# STM32G473CET6_PINOUT.net
KiCad netlist of a schematic drawn in Altium Designer
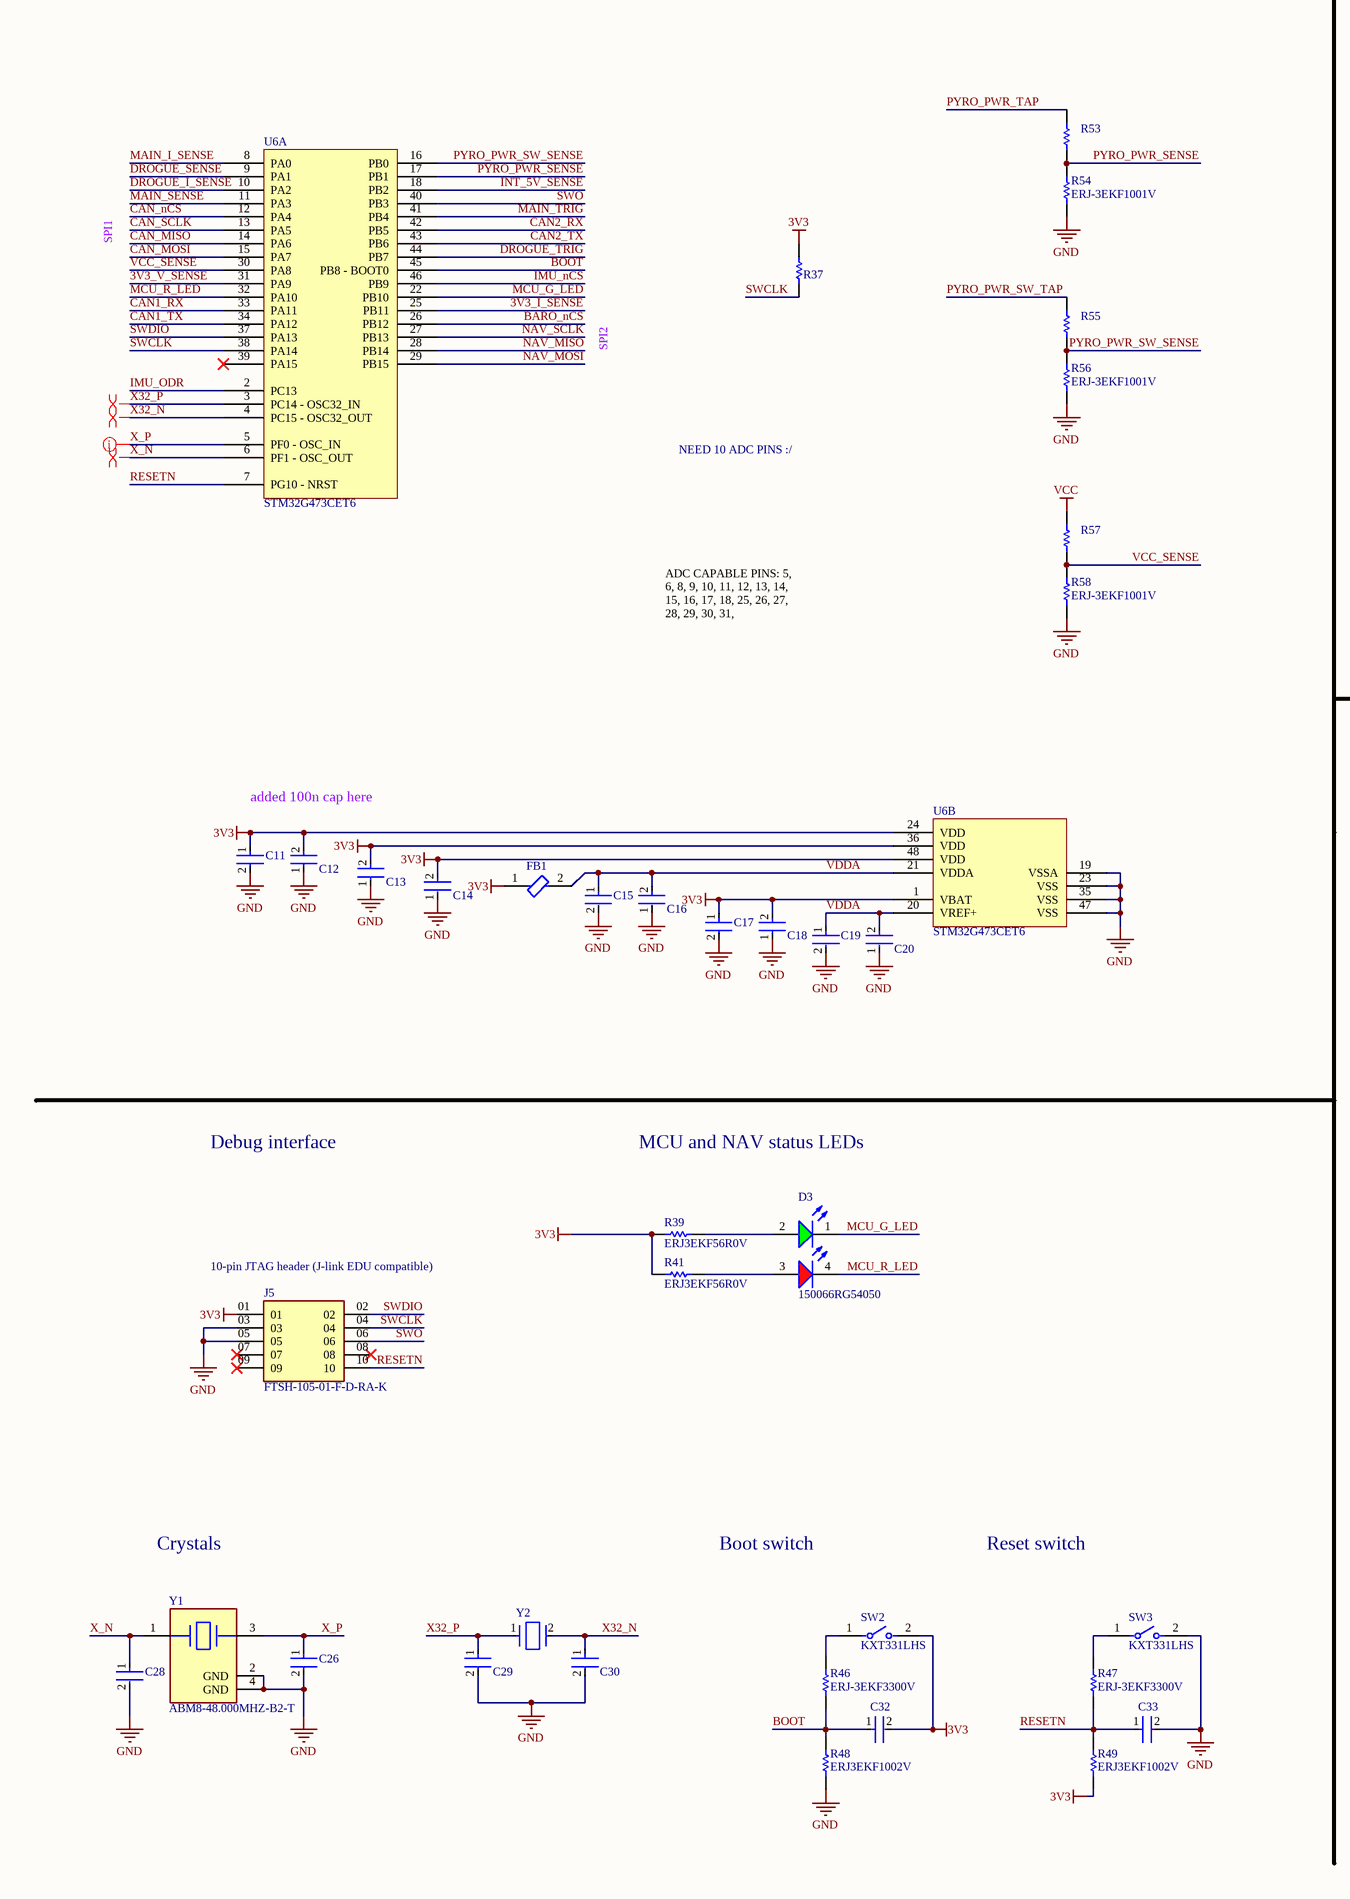
[diagram p0: STM32G473CET6_PINOUT.SchDoc, left]
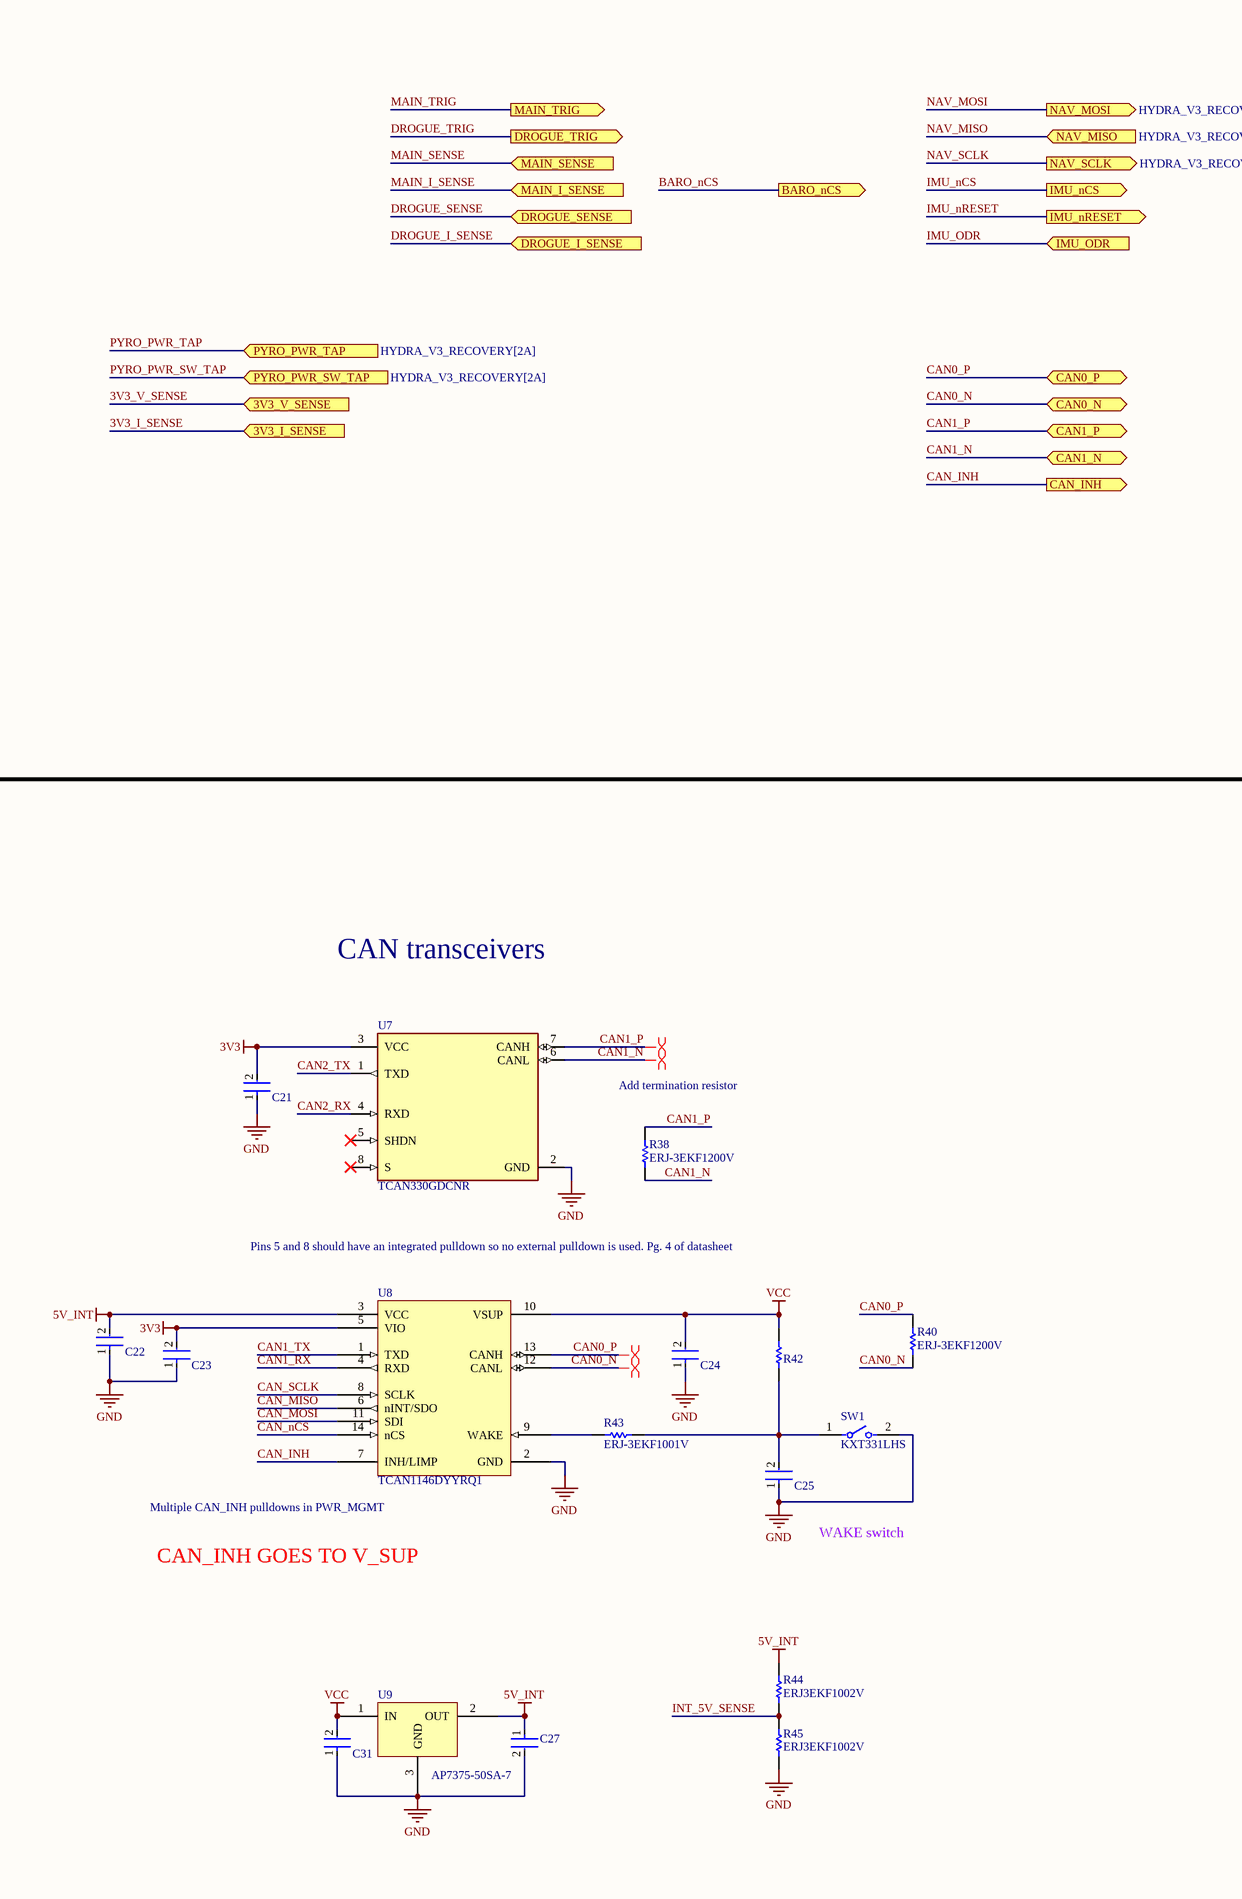
[diagram p1: STM32G473CET6_PINOUT.SchDoc, right]

(export (version "E")
  (design (tool "Eeschema 10.0.6"))
  (components
    (comp (ref "C11")
      (value "C1005X5R1A475K050BC")
      (footprint "FP-C1005-050-0_15-MFG")
      (description "CAP CER 4.7UF 10V X5R 0402")
      (fields (field (name "TOLERANCE") "10%"))
      (libsource (lib "Altium Content Vault") (part "b4654b650e69147ec39a6b967a45e02"))
    )
    (comp (ref "C12")
      (value "GRM155R71C104KA88D")
      (footprint "FP-GRM15-MFG")
      (description "CAP CER 0.1UF 16V X7R 0402")
      (fields
        (field (name "TOLERANCE") "10%")
        (field (name "OCTOPART") "https://octopart.com/grm155r71c104ka88d-murata-196880")
      )
      (libsource (lib "Altium Content Vault") (part "236180d848d6139a670b325ea6854c9"))
    )
    (comp (ref "C13")
      (value "GRM155R71C104KA88D")
      (footprint "FP-GRM15-MFG")
      (description "CAP CER 0.1UF 16V X7R 0402")
      (fields
        (field (name "TOLERANCE") "10%")
        (field (name "OCTOPART") "https://octopart.com/grm155r71c104ka88d-murata-196880")
      )
      (libsource (lib "Altium Content Vault") (part "236180d848d6139a670b325ea6854c9"))
    )
    (comp (ref "C14")
      (value "GRM155R71C104KA88D")
      (footprint "FP-GRM15-MFG")
      (description "CAP CER 0.1UF 16V X7R 0402")
      (fields
        (field (name "TOLERANCE") "10%")
        (field (name "OCTOPART") "https://octopart.com/grm155r71c104ka88d-murata-196880")
      )
      (libsource (lib "Altium Content Vault") (part "236180d848d6139a670b325ea6854c9"))
    )
    (comp (ref "C15")
      (value "EMK105BJ105KV-F")
      (footprint "FP-0402-L_1_0_0_05-W_0_5-IPC_A")
      (description "None")
      (fields (field (name "TOLERANCE") "10%"))
      (libsource (lib "Altium Content Vault") (part "b4654b650e69147ec39a6b967a45e02"))
    )
    (comp (ref "C16")
      (value "GRM155R71C104KA88D")
      (footprint "FP-GRM15-MFG")
      (description "CAP CER 0.1UF 16V X7R 0402")
      (fields
        (field (name "TOLERANCE") "10%")
        (field (name "OCTOPART") "https://octopart.com/grm155r71c104ka88d-murata-196880")
      )
      (libsource (lib "Altium Content Vault") (part "236180d848d6139a670b325ea6854c9"))
    )
    (comp (ref "C17")
      (value "EMK105BJ105KV-F")
      (footprint "FP-0402-L_1_0_0_05-W_0_5-IPC_A")
      (description "None")
      (fields (field (name "TOLERANCE") "10%"))
      (libsource (lib "Altium Content Vault") (part "b4654b650e69147ec39a6b967a45e02"))
    )
    (comp (ref "C18")
      (value "GRM155R71C104KA88D")
      (footprint "FP-GRM15-MFG")
      (description "CAP CER 0.1UF 16V X7R 0402")
      (fields
        (field (name "TOLERANCE") "10%")
        (field (name "OCTOPART") "https://octopart.com/grm155r71c104ka88d-murata-196880")
      )
      (libsource (lib "Altium Content Vault") (part "236180d848d6139a670b325ea6854c9"))
    )
    (comp (ref "C19")
      (value "EMK105BJ105KV-F")
      (footprint "FP-0402-L_1_0_0_05-W_0_5-IPC_A")
      (description "None")
      (fields (field (name "TOLERANCE") "10%"))
      (libsource (lib "Altium Content Vault") (part "b4654b650e69147ec39a6b967a45e02"))
    )
    (comp (ref "C20")
      (value "GRM155R71C104KA88D")
      (footprint "FP-GRM15-MFG")
      (description "CAP CER 0.1UF 16V X7R 0402")
      (fields
        (field (name "TOLERANCE") "10%")
        (field (name "OCTOPART") "https://octopart.com/grm155r71c104ka88d-murata-196880")
      )
      (libsource (lib "Altium Content Vault") (part "236180d848d6139a670b325ea6854c9"))
    )
    (comp (ref "C21")
      (value "C0402C104K8PACTU")
      (footprint "FP-C0402-BB-MFG")
      (description "CAP CER 0.1UF 10V X5R 0402")
      (fields (field (name "MANUFACTURER") "Kemet") (field (name "TOLERANCE") "0.1"))
      (libsource (lib "Altium Content Vault") (part "b4654b650e69147ec39a6b967a45e02"))
    )
    (comp (ref "C22")
      (value "C0402C104K8PACTU")
      (footprint "FP-C0402-BB-MFG")
      (description "CAP CER 0.1UF 10V X5R 0402")
      (fields (field (name "MANUFACTURER") "Kemet") (field (name "TOLERANCE") "0.1"))
      (libsource (lib "Altium Content Vault") (part "b4654b650e69147ec39a6b967a45e02"))
    )
    (comp (ref "C23")
      (value "C0402C104K8PACTU")
      (footprint "FP-C0402-BB-MFG")
      (description "CAP CER 0.1UF 10V X5R 0402")
      (fields (field (name "MANUFACTURER") "Kemet") (field (name "TOLERANCE") "0.1"))
      (libsource (lib "Altium Content Vault") (part "b4654b650e69147ec39a6b967a45e02"))
    )
    (comp (ref "C24")
      (value "C0402C104K8PACTU")
      (footprint "FP-C0402-BB-MFG")
      (description "CAP CER 0.1UF 10V X5R 0402")
      (fields (field (name "MANUFACTURER") "Kemet") (field (name "TOLERANCE") "0.1"))
      (libsource (lib "Altium Content Vault") (part "b4654b650e69147ec39a6b967a45e02"))
    )
    (comp (ref "C25")
      (value "C0402C104K8PACTU")
      (footprint "FP-C0402-BB-MFG")
      (description "CAP CER 0.1UF 10V X5R 0402")
      (fields (field (name "MANUFACTURER") "Kemet") (field (name "TOLERANCE") "0.1"))
      (libsource (lib "Altium Content Vault") (part "b4654b650e69147ec39a6b967a45e02"))
    )
    (comp (ref "C26")
      (value "C0402C689C5GACTU")
      (footprint "FP-C0402-BB-MFG")
      (description "CAP CER 6.8PF 50V NP0 0402")
      (fields
        (field (name "OCTOPART") "https://octopart.com/c0402c689c5gactu-kemet-9143567")
        (field (name "MANUFACTURER") "Kemet")
      )
      (libsource (lib "Altium Content Vault") (part "b4654b650e69147ec39a6b967a45e02"))
    )
    (comp (ref "C27")
      (value "CL05A106MP5NUNC")
      (footprint "FP-CL05A106MP5NUNC-MFG")
      (description "CAP CER 10UF 10V X5R 0402")
      (fields
        (field (name "OCTOPART") "https://octopart.com/cl05a106mp5nunc-samsung-22457395")
        (field (name "TOLERANCE") "20%")
      )
      (libsource (lib "Altium Content Vault") (part "b4654b650e69147ec39a6b967a45e02"))
    )
    (comp (ref "C28")
      (value "C0402C689C5GACTU")
      (footprint "FP-C0402-BB-MFG")
      (description "CAP CER 6.8PF 50V NP0 0402")
      (fields
        (field (name "OCTOPART") "https://octopart.com/c0402c689c5gactu-kemet-9143567")
        (field (name "MANUFACTURER") "Kemet")
      )
      (libsource (lib "Altium Content Vault") (part "b4654b650e69147ec39a6b967a45e02"))
    )
    (comp (ref "C29")
      (value "04025A180FAT2A")
      (footprint "FP-0402-L_1_0_1-W_0_5_0_1-IPC_A")
      (description "General Purpose Ceramic Capacitor, 0402, 18pF, 1%, C0G, 30ppm/°C, 50V")
      (fields (field (name "TOLERANCE") "1%"))
      (libsource (lib "Altium Content Vault") (part "b4654b650e69147ec39a6b967a45e02"))
    )
    (comp (ref "C30")
      (value "04025A180FAT2A")
      (footprint "FP-0402-L_1_0_1-W_0_5_0_1-IPC_A")
      (description "General Purpose Ceramic Capacitor, 0402, 18pF, 1%, C0G, 30ppm/°C, 50V")
      (fields (field (name "TOLERANCE") "1%"))
      (libsource (lib "Altium Content Vault") (part "b4654b650e69147ec39a6b967a45e02"))
    )
    (comp (ref "C31")
      (value "C0402C104K8PACTU")
      (footprint "FP-C0402-BB-MFG")
      (description "CAP CER 0.1UF 10V X5R 0402")
      (fields (field (name "MANUFACTURER") "Kemet") (field (name "TOLERANCE") "0.1"))
      (libsource (lib "Altium Content Vault") (part "b4654b650e69147ec39a6b967a45e02"))
    )
    (comp (ref "C32")
      (value "C0402C104K8PACTU")
      (footprint "FP-C0402-BB-MFG")
      (description "CAP CER 0.1UF 10V X5R 0402")
      (fields (field (name "MANUFACTURER") "Kemet") (field (name "TOLERANCE") "0.1"))
      (libsource (lib "Altium Content Vault") (part "b4654b650e69147ec39a6b967a45e02"))
    )
    (comp (ref "C33")
      (value "C0402C104K8PACTU")
      (footprint "FP-C0402-BB-MFG")
      (description "CAP CER 0.1UF 10V X5R 0402")
      (fields (field (name "MANUFACTURER") "Kemet") (field (name "TOLERANCE") "0.1"))
      (libsource (lib "Altium Content Vault") (part "b4654b650e69147ec39a6b967a45e02"))
    )
    (comp (ref "D3")
      (value "150066RG54050")
      (footprint "WL-SBCD_0606")
      (description "Led, Red/Grn, 180Mcd/230Mcd, 624Nm/525Nm Rohs Compliant: Yes")
      (fields (field (name "SOURCE") "rgled.SchLib"))
      (libsource (lib "Space Concordia") (part "CMP-004-00034-2"))
    )
    (comp (ref "FB1")
      (value "BLM15PX601SN1D")
      (footprint "FP-BLM15-0_05-MFG")
      (description "Chip Ferrite Bead, 0402, 600Ω @ 100MHz, 0.23Ω, 25%, 900mA")
      (fields (field (name "TOLERANCE") "25%"))
      (libsource (lib "Altium Content Vault") (part "5f30dd21d616792df468990f7003faa"))
    )
    (comp (ref "J5")
      (value "FTSH-105-01-F-D-RA-K")
      (footprint "FTSH-105-01-F-D-RA-K-Footprint-1")
      (libsource (lib "Space Concordia") (part "FTSH-105-01-F-D-RA-K-Symbol-1"))
    )
    (comp (ref "R37")
      (value "ERJ3EKF1002V")
      (footprint "RESC1609X55X30LL15T15")
      (description "Chip Resistor, 10 KOhm, +/- 1%, 0.1 W, -55 to 155 degC, 0603 (1608 Metric), RoHS, Tape and Reel")
      (fields (field (name "TOLERANCE") "1%") (field (name "MANUFACTURER") "Panasonic"))
      (libsource (lib "Altium Content Vault") (part "RES-2"))
    )
    (comp (ref "R38")
      (value "ERJ-3EKF1200V")
      (footprint "RESC1609X55X30ML15T15")
      (description "Chip Resistor, 120 Ohm, +/- 1%, 0.1 W, -55 to 155 degC, 0603 (1608 Metric), RoHS, Tape and Reel")
      (fields (field (name "TOLERANCE") "1%") (field (name "MANUFACTURER") "Panasonic"))
      (libsource (lib "Altium Content Vault") (part "RES-2"))
    )
    (comp (ref "R39")
      (value "ERJ3EKF56R0V")
      (footprint "RESC1608X55X30NL15T15")
      (fields (field (name "MANUFACTURER") "Panasonic"))
      (libsource (lib "Altium Content Vault") (part "RES"))
    )
    (comp (ref "R40")
      (value "ERJ-3EKF1200V")
      (footprint "RESC1609X55X30ML15T15")
      (description "Chip Resistor, 120 Ohm, +/- 1%, 0.1 W, -55 to 155 degC, 0603 (1608 Metric), RoHS, Tape and Reel")
      (fields (field (name "TOLERANCE") "1%") (field (name "MANUFACTURER") "Panasonic"))
      (libsource (lib "Altium Content Vault") (part "RES-2"))
    )
    (comp (ref "R41")
      (value "ERJ3EKF56R0V")
      (footprint "RESC1608X55X30NL15T15")
      (fields (field (name "MANUFACTURER") "Panasonic"))
      (libsource (lib "Altium Content Vault") (part "RES"))
    )
    (comp (ref "R42")
      (value "ERJ3EKF1002V")
      (footprint "RESC1609X55X30LL15T15")
      (description "Chip Resistor, 10 KOhm, +/- 1%, 0.1 W, -55 to 155 degC, 0603 (1608 Metric), RoHS, Tape and Reel")
      (fields (field (name "TOLERANCE") "1%") (field (name "MANUFACTURER") "Panasonic"))
      (libsource (lib "Altium Content Vault") (part "RES-2"))
    )
    (comp (ref "R43")
      (value "ERJ-3EKF1001V")
      (footprint "RESC1608X55X30LL15T15")
      (fields (field (name "MANUFACTURER") "Panasonic"))
      (libsource (lib "Altium Content Vault") (part "RES"))
    )
    (comp (ref "R44")
      (value "ERJ3EKF1002V")
      (footprint "RESC1609X55X30LL15T15")
      (description "Chip Resistor, 10 KOhm, +/- 1%, 0.1 W, -55 to 155 degC, 0603 (1608 Metric), RoHS, Tape and Reel")
      (fields (field (name "TOLERANCE") "1%") (field (name "MANUFACTURER") "Panasonic"))
      (libsource (lib "Altium Content Vault") (part "RES-2"))
    )
    (comp (ref "R45")
      (value "ERJ3EKF1002V")
      (footprint "RESC1609X55X30LL15T15")
      (description "Chip Resistor, 10 KOhm, +/- 1%, 0.1 W, -55 to 155 degC, 0603 (1608 Metric), RoHS, Tape and Reel")
      (fields (field (name "TOLERANCE") "1%") (field (name "MANUFACTURER") "Panasonic"))
      (libsource (lib "Altium Content Vault") (part "RES-2"))
    )
    (comp (ref "R46")
      (value "ERJ-3EKF3300V")
      (footprint "RESC1608X55X30LL15T15")
      (description "Chip Resistor, 330 Ohm, +/- 1%, 0.1 W, -55 to 155 degC, 0603 (1608 Metric), RoHS, Tape and Reel")
      (libsource (lib "Altium Content Vault") (part "RES-2"))
    )
    (comp (ref "R47")
      (value "ERJ-3EKF3300V")
      (footprint "RESC1608X55X30LL15T15")
      (description "Chip Resistor, 330 Ohm, +/- 1%, 0.1 W, -55 to 155 degC, 0603 (1608 Metric), RoHS, Tape and Reel")
      (libsource (lib "Altium Content Vault") (part "RES-2"))
    )
    (comp (ref "R48")
      (value "ERJ3EKF1002V")
      (footprint "RESC1609X55X30LL15T15")
      (description "Chip Resistor, 10 KOhm, +/- 1%, 0.1 W, -55 to 155 degC, 0603 (1608 Metric), RoHS, Tape and Reel")
      (fields (field (name "TOLERANCE") "1%") (field (name "MANUFACTURER") "Panasonic"))
      (libsource (lib "Altium Content Vault") (part "RES-2"))
    )
    (comp (ref "R49")
      (value "ERJ3EKF1002V")
      (footprint "RESC1609X55X30LL15T15")
      (description "Chip Resistor, 10 KOhm, +/- 1%, 0.1 W, -55 to 155 degC, 0603 (1608 Metric), RoHS, Tape and Reel")
      (fields (field (name "TOLERANCE") "1%") (field (name "MANUFACTURER") "Panasonic"))
      (libsource (lib "Altium Content Vault") (part "RES-2"))
    )
    (comp (ref "R53")
      (value "ERJ3EKF1002V")
      (footprint "RESC1609X55X30LL15T15")
      (description "Chip Resistor, 10 KOhm, +/- 1%, 0.1 W, -55 to 155 degC, 0603 (1608 Metric), RoHS, Tape and Reel")
      (fields (field (name "TOLERANCE") "1%") (field (name "MANUFACTURER") "Panasonic"))
      (libsource (lib "Altium Content Vault") (part "RES-2"))
    )
    (comp (ref "R54")
      (value "ERJ-3EKF1001V")
      (footprint "RESC1608X55X30LL15T15")
      (fields (field (name "MANUFACTURER") "Panasonic"))
      (libsource (lib "Altium Content Vault") (part "RES"))
    )
    (comp (ref "R55")
      (value "ERJ3EKF1002V")
      (footprint "RESC1609X55X30LL15T15")
      (description "Chip Resistor, 10 KOhm, +/- 1%, 0.1 W, -55 to 155 degC, 0603 (1608 Metric), RoHS, Tape and Reel")
      (fields (field (name "TOLERANCE") "1%") (field (name "MANUFACTURER") "Panasonic"))
      (libsource (lib "Altium Content Vault") (part "RES-2"))
    )
    (comp (ref "R56")
      (value "ERJ-3EKF1001V")
      (footprint "RESC1608X55X30LL15T15")
      (fields (field (name "MANUFACTURER") "Panasonic"))
      (libsource (lib "Altium Content Vault") (part "RES"))
    )
    (comp (ref "R57")
      (value "ERJ3EKF1002V")
      (footprint "RESC1609X55X30LL15T15")
      (description "Chip Resistor, 10 KOhm, +/- 1%, 0.1 W, -55 to 155 degC, 0603 (1608 Metric), RoHS, Tape and Reel")
      (fields (field (name "TOLERANCE") "1%") (field (name "MANUFACTURER") "Panasonic"))
      (libsource (lib "Altium Content Vault") (part "RES-2"))
    )
    (comp (ref "R58")
      (value "ERJ-3EKF1001V")
      (footprint "RESC1608X55X30LL15T15")
      (fields (field (name "MANUFACTURER") "Panasonic"))
      (libsource (lib "Altium Content Vault") (part "RES"))
    )
    (comp (ref "SW1")
      (value "KXT331LHS")
      (footprint "FP-KXT331LHS-MFG")
      (description "SWITCH TACTILE SPST-NO 0.02A 15V")
      (libsource (lib "Altium Content Vault") (part "bb27bde45df87f1f469753f287ef5ae"))
    )
    (comp (ref "SW2")
      (value "KXT331LHS")
      (footprint "FP-KXT331LHS-MFG")
      (description "SWITCH TACTILE SPST-NO 0.02A 15V")
      (libsource (lib "Altium Content Vault") (part "bb27bde45df87f1f469753f287ef5ae"))
    )
    (comp (ref "SW3")
      (value "KXT331LHS")
      (footprint "FP-KXT331LHS-MFG")
      (description "SWITCH TACTILE SPST-NO 0.02A 15V")
      (libsource (lib "Altium Content Vault") (part "bb27bde45df87f1f469753f287ef5ae"))
    )
    (comp (ref "U6")
      (value "STM32G473CET6")
      (footprint "TSQFP50P900X900X160-48N")
      (description "RISC Microcontroller, 32-Bit, 170MHz")
      (libsource (lib "Space Concordia") (part "STM32G473CET6"))
    )
    (comp (ref "U7")
      (value "TCAN330GDCNR")
      (footprint "FP-DCN0008A-MFG")
      (description "IC TRANSCEIVER 1/1 SOT23-8")
      (libsource (lib "Altium Content Vault") (part "22681b49c22ad38c6a4e12e04c36c7a"))
    )
    (comp (ref "U8")
      (value "TCAN1146DYYRQ1")
      (footprint "TCAN1146DYYRQ1-Footprint-1")
      (libsource (lib "Space Concordia") (part "CMP-015-00012-2"))
    )
    (comp (ref "U9")
      (value "AP7375-50SA-7")
      (footprint "AP7375-50SA-7-Footprint-1")
      (description "Ldo Cmos Lowcurr SOT23 T&r 3K")
      (libsource (lib "Space Concordia") (part "AP7375-50SA-7"))
    )
    (comp (ref "Y1")
      (value "ABM8-48.000MHZ-B2-T")
      (footprint "FP-ABM8-MFG")
      (description "Crystal 48MHz ±20ppm 18pF SMD-4 3.2mm x 2.5mm")
      (fields (field (name "TOLERANCE") "20ppm"))
      (libsource (lib "Altium Content Vault") (part "dfdb7f9a12507849fb681da9a70121c"))
    )
    (comp (ref "Y2")
      (value "ECS-.327-12.5-1210-TR")
      (footprint "FP-ECX-1210-MFG")
      (description "CRYSTAL 32.7680KHZ 12.5PF SMD")
      (fields
        (field (name "OCTOPART") "https://octopart.com/ecs-.327-12.5-1210-tr-ecs+international-81221340")
        (field (name "TOLERANCE") "20ppm")
      )
      (libsource (lib "Altium Content Vault") (part "99724985039315a44fd0d1401b84e49"))
    )
  )
  (nets
    (net (code "1") (name "/3V3_I_SENSE") (class "Default")
      (node (ref "U6") (pin "25") (pinfunction "PB11_25") (pintype "passive"))
    )
    (net (code "2") (name "/3V3_V_SENSE") (class "Default")
      (node (ref "U6") (pin "31") (pinfunction "PA9_31") (pintype "passive"))
    )
    (net (code "3") (name "/BARO_nCS") (class "Default")
      (node (ref "U6") (pin "26") (pinfunction "PB12_26") (pintype "passive"))
    )
    (net (code "4") (name "/BOOT") (class "Default")
      (node (ref "C32") (pin "1") (pinfunction "1_1") (pintype "passive"))
      (node (ref "R46") (pin "1") (pinfunction "1_1") (pintype "passive"))
      (node (ref "R48") (pin "2") (pinfunction "2_2") (pintype "passive"))
      (node (ref "U6") (pin "45") (pinfunction "PB8_-_BOOT0_45") (pintype "passive"))
    )
    (net (code "5") (name "/CAN0_N") (class "Default")
      (node (ref "R40") (pin "2") (pinfunction "2_2") (pintype "passive"))
      (node (ref "U8") (pin "12") (pinfunction "CANL_12") (pintype "bidirectional"))
    )
    (net (code "6") (name "/CAN0_P") (class "Default")
      (node (ref "R40") (pin "1") (pinfunction "1_1") (pintype "passive"))
      (node (ref "U8") (pin "13") (pinfunction "CANH_13") (pintype "bidirectional"))
    )
    (net (code "7") (name "/CAN1_N") (class "Default")
      (node (ref "R38") (pin "1") (pinfunction "1_1") (pintype "passive"))
      (node (ref "U7") (pin "6") (pinfunction "CANL_6") (pintype "bidirectional"))
    )
    (net (code "8") (name "/CAN1_P") (class "Default")
      (node (ref "R38") (pin "2") (pinfunction "2_2") (pintype "passive"))
      (node (ref "U7") (pin "7") (pinfunction "CANH_7") (pintype "bidirectional"))
    )
    (net (code "9") (name "/CAN1_RX") (class "Default")
      (node (ref "U6") (pin "33") (pinfunction "PA11_33") (pintype "passive"))
      (node (ref "U8") (pin "4") (pinfunction "RXD_4") (pintype "output"))
    )
    (net (code "10") (name "/CAN1_TX") (class "Default")
      (node (ref "U6") (pin "34") (pinfunction "PA12_34") (pintype "passive"))
      (node (ref "U8") (pin "1") (pinfunction "TXD_1") (pintype "input"))
    )
    (net (code "11") (name "/CAN2_RX") (class "Default")
      (node (ref "U6") (pin "42") (pinfunction "PB5_42") (pintype "passive"))
      (node (ref "U7") (pin "4") (pinfunction "RXD_4") (pintype "input"))
    )
    (net (code "12") (name "/CAN2_TX") (class "Default")
      (node (ref "U6") (pin "43") (pinfunction "PB6_43") (pintype "passive"))
      (node (ref "U7") (pin "1") (pinfunction "TXD_1") (pintype "output"))
    )
    (net (code "13") (name "/CAN_INH") (class "Default")
      (node (ref "U8") (pin "7") (pinfunction "INH/LIMP_7") (pintype "passive"))
    )
    (net (code "14") (name "/CAN_MISO") (class "Default")
      (node (ref "U6") (pin "14") (pinfunction "PA6_14") (pintype "passive"))
      (node (ref "U8") (pin "6") (pinfunction "nINT/SDO_6") (pintype "output"))
    )
    (net (code "15") (name "/CAN_MOSI") (class "Default")
      (node (ref "U6") (pin "15") (pinfunction "PA7_15") (pintype "passive"))
      (node (ref "U8") (pin "11") (pinfunction "SDI_11") (pintype "input"))
    )
    (net (code "16") (name "/CAN_SCLK") (class "Default")
      (node (ref "U6") (pin "13") (pinfunction "PA5_13") (pintype "passive"))
      (node (ref "U8") (pin "8") (pinfunction "SCLK_8") (pintype "input"))
    )
    (net (code "17") (name "/CAN_nCS") (class "Default")
      (node (ref "U6") (pin "12") (pinfunction "PA4_12") (pintype "passive"))
      (node (ref "U8") (pin "14") (pinfunction "nCS_14") (pintype "input"))
    )
    (net (code "18") (name "/DROGUE_I_SENSE") (class "Default")
      (node (ref "U6") (pin "10") (pinfunction "PA2_10") (pintype "passive"))
    )
    (net (code "19") (name "/DROGUE_SENSE") (class "Default")
      (node (ref "U6") (pin "9") (pinfunction "PA1_9") (pintype "passive"))
    )
    (net (code "20") (name "/DROGUE_TRIG") (class "Default")
      (node (ref "U6") (pin "44") (pinfunction "PB7_44") (pintype "passive"))
    )
    (net (code "21") (name "/IMU_ODR") (class "Default")
      (node (ref "U6") (pin "2") (pinfunction "PC13_2") (pintype "passive"))
    )
    (net (code "22") (name "/IMU_nCS") (class "Default")
      (node (ref "U6") (pin "46") (pinfunction "PB9_46") (pintype "passive"))
    )
    (net (code "24") (name "/INT_5V_SENSE") (class "Default")
      (node (ref "R44") (pin "1") (pinfunction "1_1") (pintype "passive"))
      (node (ref "R45") (pin "1") (pinfunction "1_1") (pintype "passive"))
      (node (ref "U6") (pin "18") (pinfunction "PB2_18") (pintype "passive"))
    )
    (net (code "25") (name "/MAIN_I_SENSE") (class "Default")
      (node (ref "U6") (pin "8") (pinfunction "PA0_8") (pintype "passive"))
    )
    (net (code "26") (name "/MAIN_SENSE") (class "Default")
      (node (ref "U6") (pin "11") (pinfunction "PA3_11") (pintype "passive"))
    )
    (net (code "27") (name "/MAIN_TRIG") (class "Default")
      (node (ref "U6") (pin "41") (pinfunction "PB4_41") (pintype "passive"))
    )
    (net (code "28") (name "/MCU_G_LED") (class "Default")
      (node (ref "D3") (pin "1") (pinfunction "K_1") (pintype "passive"))
      (node (ref "U6") (pin "22") (pinfunction "PB10_22") (pintype "passive"))
    )
    (net (code "29") (name "/MCU_R_LED") (class "Default")
      (node (ref "D3") (pin "4") (pinfunction "K_4") (pintype "passive"))
      (node (ref "U6") (pin "32") (pinfunction "PA10_32") (pintype "passive"))
    )
    (net (code "30") (name "/NAV_MISO") (class "Default")
      (node (ref "U6") (pin "28") (pinfunction "PB14_28") (pintype "passive"))
    )
    (net (code "31") (name "/NAV_MOSI") (class "Default")
      (node (ref "U6") (pin "29") (pinfunction "PB15_29") (pintype "passive"))
    )
    (net (code "32") (name "/NAV_SCLK") (class "Default")
      (node (ref "U6") (pin "27") (pinfunction "PB13_27") (pintype "passive"))
    )
    (net (code "33") (name "/PYRO_PWR_SENSE") (class "Default")
      (node (ref "R53") (pin "2") (pinfunction "2_2") (pintype "passive"))
      (node (ref "R54") (pin "1") (pinfunction "1_1") (pintype "passive"))
      (node (ref "U6") (pin "17") (pinfunction "PB1_17") (pintype "passive"))
    )
    (net (code "34") (name "/PYRO_PWR_SW_SENSE") (class "Default")
      (node (ref "R55") (pin "2") (pinfunction "2_2") (pintype "passive"))
      (node (ref "R56") (pin "1") (pinfunction "1_1") (pintype "passive"))
      (node (ref "U6") (pin "16") (pinfunction "PB0_16") (pintype "passive"))
    )
    (net (code "35") (name "/PYRO_PWR_SW_TAP") (class "Default")
      (node (ref "R55") (pin "1") (pinfunction "1_1") (pintype "passive"))
    )
    (net (code "36") (name "/PYRO_PWR_TAP") (class "Default")
      (node (ref "R53") (pin "1") (pinfunction "1_1") (pintype "passive"))
    )
    (net (code "37") (name "/RESETN") (class "Default")
      (node (ref "C33") (pin "1") (pinfunction "1_1") (pintype "passive"))
      (node (ref "J5") (pin "10") (pinfunction "10_10") (pintype "passive"))
      (node (ref "R47") (pin "1") (pinfunction "1_1") (pintype "passive"))
      (node (ref "R49") (pin "2") (pinfunction "2_2") (pintype "passive"))
      (node (ref "U6") (pin "7") (pinfunction "PG10_-_NRST_7") (pintype "passive"))
    )
    (net (code "38") (name "/SWCLK") (class "Default")
      (node (ref "J5") (pin "04") (pinfunction "04_04") (pintype "passive"))
      (node (ref "R37") (pin "2") (pinfunction "2_2") (pintype "passive"))
      (node (ref "U6") (pin "38") (pinfunction "PA14_38") (pintype "passive"))
    )
    (net (code "39") (name "/SWDIO") (class "Default")
      (node (ref "J5") (pin "02") (pinfunction "02_02") (pintype "passive"))
      (node (ref "U6") (pin "37") (pinfunction "PA13_37") (pintype "passive"))
    )
    (net (code "40") (name "/SWO") (class "Default")
      (node (ref "J5") (pin "06") (pinfunction "06_06") (pintype "passive"))
      (node (ref "U6") (pin "40") (pinfunction "PB3_40") (pintype "passive"))
    )
    (net (code "41") (name "/VCC_SENSE") (class "Default")
      (node (ref "R57") (pin "2") (pinfunction "2_2") (pintype "passive"))
      (node (ref "R58") (pin "1") (pinfunction "1_1") (pintype "passive"))
      (node (ref "U6") (pin "30") (pinfunction "PA8_30") (pintype "passive"))
    )
    (net (code "42") (name "/VDDA") (class "Default")
      (node (ref "C15") (pin "1") (pinfunction "1_1") (pintype "passive"))
      (node (ref "C16") (pin "2") (pinfunction "2_2") (pintype "passive"))
      (node (ref "C19") (pin "1") (pinfunction "1_1") (pintype "passive"))
      (node (ref "C20") (pin "2") (pinfunction "2_2") (pintype "passive"))
      (node (ref "FB1") (pin "2") (pinfunction "2_2") (pintype "passive"))
      (node (ref "U6") (pin "20") (pinfunction "VREF+_20") (pintype "passive"))
      (node (ref "U6") (pin "21") (pinfunction "VDDA_21") (pintype "passive"))
    )
    (net (code "43") (name "/X32_N") (class "Default")
      (node (ref "C30") (pin "1") (pinfunction "1_1") (pintype "passive"))
      (node (ref "U6") (pin "4") (pinfunction "PC15_-_OSC32_OUT_4") (pintype "passive"))
      (node (ref "Y2") (pin "2") (pinfunction "Out/In_2") (pintype "passive"))
    )
    (net (code "44") (name "/X32_P") (class "Default")
      (node (ref "C29") (pin "1") (pinfunction "1_1") (pintype "passive"))
      (node (ref "U6") (pin "3") (pinfunction "PC14_-_OSC32_IN_3") (pintype "passive"))
      (node (ref "Y2") (pin "1") (pinfunction "In/Out_1") (pintype "passive"))
    )
    (net (code "45") (name "/X_N") (class "Default")
      (node (ref "C28") (pin "1") (pinfunction "1_1") (pintype "passive"))
      (node (ref "U6") (pin "6") (pinfunction "PF1_-_OSC_OUT_6") (pintype "passive"))
      (node (ref "Y1") (pin "1") (pinfunction "1_1") (pintype "passive"))
    )
    (net (code "46") (name "/X_P") (class "Default")
      (node (ref "C26") (pin "1") (pinfunction "1_1") (pintype "passive"))
      (node (ref "U6") (pin "5") (pinfunction "PF0_-_OSC_IN_5") (pintype "passive"))
      (node (ref "Y1") (pin "3") (pinfunction "3_3") (pintype "passive"))
    )
    (net (code "47") (name "3V3") (class "Default")
      (node (ref "C11") (pin "1") (pinfunction "1_1") (pintype "passive"))
      (node (ref "C12") (pin "2") (pinfunction "2_2") (pintype "passive"))
      (node (ref "C13") (pin "2") (pinfunction "2_2") (pintype "passive"))
      (node (ref "C14") (pin "2") (pinfunction "2_2") (pintype "passive"))
      (node (ref "C17") (pin "1") (pinfunction "1_1") (pintype "passive"))
      (node (ref "C18") (pin "2") (pinfunction "2_2") (pintype "passive"))
      (node (ref "C21") (pin "2") (pinfunction "2_2") (pintype "passive"))
      (node (ref "C23") (pin "2") (pinfunction "2_2") (pintype "passive"))
      (node (ref "C32") (pin "2") (pinfunction "2_2") (pintype "passive"))
      (node (ref "FB1") (pin "1") (pinfunction "1_1") (pintype "passive"))
      (node (ref "J5") (pin "01") (pinfunction "01_01") (pintype "passive"))
      (node (ref "R37") (pin "1") (pinfunction "1_1") (pintype "passive"))
      (node (ref "R39") (pin "2") (pinfunction "2_2") (pintype "passive"))
      (node (ref "R41") (pin "2") (pinfunction "2_2") (pintype "passive"))
      (node (ref "R49") (pin "1") (pinfunction "1_1") (pintype "passive"))
      (node (ref "SW2") (pin "2") (pinfunction "2_2") (pintype "passive"))
      (node (ref "U6") (pin "1") (pinfunction "VBAT_1") (pintype "passive"))
      (node (ref "U6") (pin "24") (pinfunction "VDD_24") (pintype "passive"))
      (node (ref "U6") (pin "36") (pinfunction "VDD_36") (pintype "passive"))
      (node (ref "U6") (pin "48") (pinfunction "VDD_48") (pintype "passive"))
      (node (ref "U7") (pin "3") (pinfunction "VCC_3") (pintype "power_in"))
      (node (ref "U8") (pin "5") (pinfunction "VIO_5") (pintype "power_in"))
    )
    (net (code "48") (name "5V_INT") (class "Default")
      (node (ref "C22") (pin "2") (pinfunction "2_2") (pintype "passive"))
      (node (ref "C27") (pin "1") (pinfunction "1_1") (pintype "passive"))
      (node (ref "R44") (pin "2") (pinfunction "2_2") (pintype "passive"))
      (node (ref "U8") (pin "3") (pinfunction "VCC_3") (pintype "power_in"))
      (node (ref "U9") (pin "2") (pinfunction "OUT_2") (pintype "passive"))
    )
    (net (code "49") (name "GND") (class "Default")
      (node (ref "C11") (pin "2") (pinfunction "2_2") (pintype "passive"))
      (node (ref "C12") (pin "1") (pinfunction "1_1") (pintype "passive"))
      (node (ref "C13") (pin "1") (pinfunction "1_1") (pintype "passive"))
      (node (ref "C14") (pin "1") (pinfunction "1_1") (pintype "passive"))
      (node (ref "C15") (pin "2") (pinfunction "2_2") (pintype "passive"))
      (node (ref "C16") (pin "1") (pinfunction "1_1") (pintype "passive"))
      (node (ref "C17") (pin "2") (pinfunction "2_2") (pintype "passive"))
      (node (ref "C18") (pin "1") (pinfunction "1_1") (pintype "passive"))
      (node (ref "C19") (pin "2") (pinfunction "2_2") (pintype "passive"))
      (node (ref "C20") (pin "1") (pinfunction "1_1") (pintype "passive"))
      (node (ref "C21") (pin "1") (pinfunction "1_1") (pintype "passive"))
      (node (ref "C22") (pin "1") (pinfunction "1_1") (pintype "passive"))
      (node (ref "C23") (pin "1") (pinfunction "1_1") (pintype "passive"))
      (node (ref "C24") (pin "1") (pinfunction "1_1") (pintype "passive"))
      (node (ref "C25") (pin "1") (pinfunction "1_1") (pintype "passive"))
      (node (ref "C26") (pin "2") (pinfunction "2_2") (pintype "passive"))
      (node (ref "C27") (pin "2") (pinfunction "2_2") (pintype "passive"))
      (node (ref "C28") (pin "2") (pinfunction "2_2") (pintype "passive"))
      (node (ref "C29") (pin "2") (pinfunction "2_2") (pintype "passive"))
      (node (ref "C30") (pin "2") (pinfunction "2_2") (pintype "passive"))
      (node (ref "C31") (pin "1") (pinfunction "1_1") (pintype "passive"))
      (node (ref "C33") (pin "2") (pinfunction "2_2") (pintype "passive"))
      (node (ref "J5") (pin "03") (pinfunction "03_03") (pintype "passive"))
      (node (ref "J5") (pin "05") (pinfunction "05_05") (pintype "passive"))
      (node (ref "R45") (pin "2") (pinfunction "2_2") (pintype "passive"))
      (node (ref "R48") (pin "1") (pinfunction "1_1") (pintype "passive"))
      (node (ref "R54") (pin "2") (pinfunction "2_2") (pintype "passive"))
      (node (ref "R56") (pin "2") (pinfunction "2_2") (pintype "passive"))
      (node (ref "R58") (pin "2") (pinfunction "2_2") (pintype "passive"))
      (node (ref "SW1") (pin "2") (pinfunction "2_2") (pintype "passive"))
      (node (ref "SW3") (pin "2") (pinfunction "2_2") (pintype "passive"))
      (node (ref "U6") (pin "19") (pinfunction "VSSA_19") (pintype "passive"))
      (node (ref "U6") (pin "23") (pinfunction "VSS_23") (pintype "passive"))
      (node (ref "U6") (pin "35") (pinfunction "VSS_35") (pintype "passive"))
      (node (ref "U6") (pin "47") (pinfunction "VSS_47") (pintype "passive"))
      (node (ref "U7") (pin "2") (pinfunction "GND_2") (pintype "power_in"))
      (node (ref "U8") (pin "2") (pinfunction "GND_2") (pintype "power_in"))
      (node (ref "U9") (pin "3") (pinfunction "GND_3") (pintype "passive"))
      (node (ref "Y1") (pin "2") (pinfunction "GND_2") (pintype "power_in"))
      (node (ref "Y1") (pin "4") (pinfunction "GND_4") (pintype "power_in"))
    )
    (net (code "50") (name "Net-(C25-Pad2)") (class "Default")
      (node (ref "C25") (pin "2") (pinfunction "2_2") (pintype "passive"))
      (node (ref "R42") (pin "2") (pinfunction "2_2") (pintype "passive"))
      (node (ref "R43") (pin "2") (pinfunction "2_2") (pintype "passive"))
      (node (ref "SW1") (pin "1") (pinfunction "1_1") (pintype "passive"))
    )
    (net (code "51") (name "Net-(D3-A-Pad2)") (class "Default")
      (node (ref "D3") (pin "2") (pinfunction "A_2") (pintype "passive"))
      (node (ref "R39") (pin "1") (pinfunction "1_1") (pintype "passive"))
    )
    (net (code "52") (name "Net-(D3-A-Pad3)") (class "Default")
      (node (ref "D3") (pin "3") (pinfunction "A_3") (pintype "passive"))
      (node (ref "R41") (pin "1") (pinfunction "1_1") (pintype "passive"))
    )
    (net (code "53") (name "Net-(R46-Pad2)") (class "Default")
      (node (ref "R46") (pin "2") (pinfunction "2_2") (pintype "passive"))
      (node (ref "SW2") (pin "1") (pinfunction "1_1") (pintype "passive"))
    )
    (net (code "54") (name "Net-(R47-Pad2)") (class "Default")
      (node (ref "R47") (pin "2") (pinfunction "2_2") (pintype "passive"))
      (node (ref "SW3") (pin "1") (pinfunction "1_1") (pintype "passive"))
    )
    (net (code "55") (name "Net-(U8-WAKE)") (class "Default")
      (node (ref "R43") (pin "1") (pinfunction "1_1") (pintype "passive"))
      (node (ref "U8") (pin "9") (pinfunction "WAKE_9") (pintype "input"))
    )
    (net (code "56") (name "VCC") (class "Default")
      (node (ref "C24") (pin "2") (pinfunction "2_2") (pintype "passive"))
      (node (ref "C31") (pin "2") (pinfunction "2_2") (pintype "passive"))
      (node (ref "R42") (pin "1") (pinfunction "1_1") (pintype "passive"))
      (node (ref "R57") (pin "1") (pinfunction "1_1") (pintype "passive"))
      (node (ref "U8") (pin "10") (pinfunction "VSUP_10") (pintype "power_in"))
      (node (ref "U9") (pin "1") (pinfunction "IN_1") (pintype "passive"))
    )
    (net (code "57") (name "unconnected-(J5-Pad07)") (class "Default")
      (node (ref "J5") (pin "07") (pinfunction "07_07") (pintype "passive+no_connect"))
    )
    (net (code "58") (name "unconnected-(J5-Pad08)") (class "Default")
      (node (ref "J5") (pin "08") (pinfunction "08_08") (pintype "passive+no_connect"))
    )
    (net (code "59") (name "unconnected-(J5-Pad09)") (class "Default")
      (node (ref "J5") (pin "09") (pinfunction "09_09") (pintype "passive+no_connect"))
    )
    (net (code "60") (name "unconnected-(U6A-PA15-Pad39)") (class "Default")
      (node (ref "U6") (pin "39") (pinfunction "PA15_39") (pintype "passive+no_connect"))
    )
    (net (code "61") (name "unconnected-(U7-S-Pad8)") (class "Default")
      (node (ref "U7") (pin "8") (pinfunction "S_8") (pintype "input+no_connect"))
    )
    (net (code "62") (name "unconnected-(U7-SHDN-Pad5)") (class "Default")
      (node (ref "U7") (pin "5") (pinfunction "SHDN_5") (pintype "input+no_connect"))
    )
  )
)
